# node.net
KiCad netlist of a schematic drawn in EAGLE
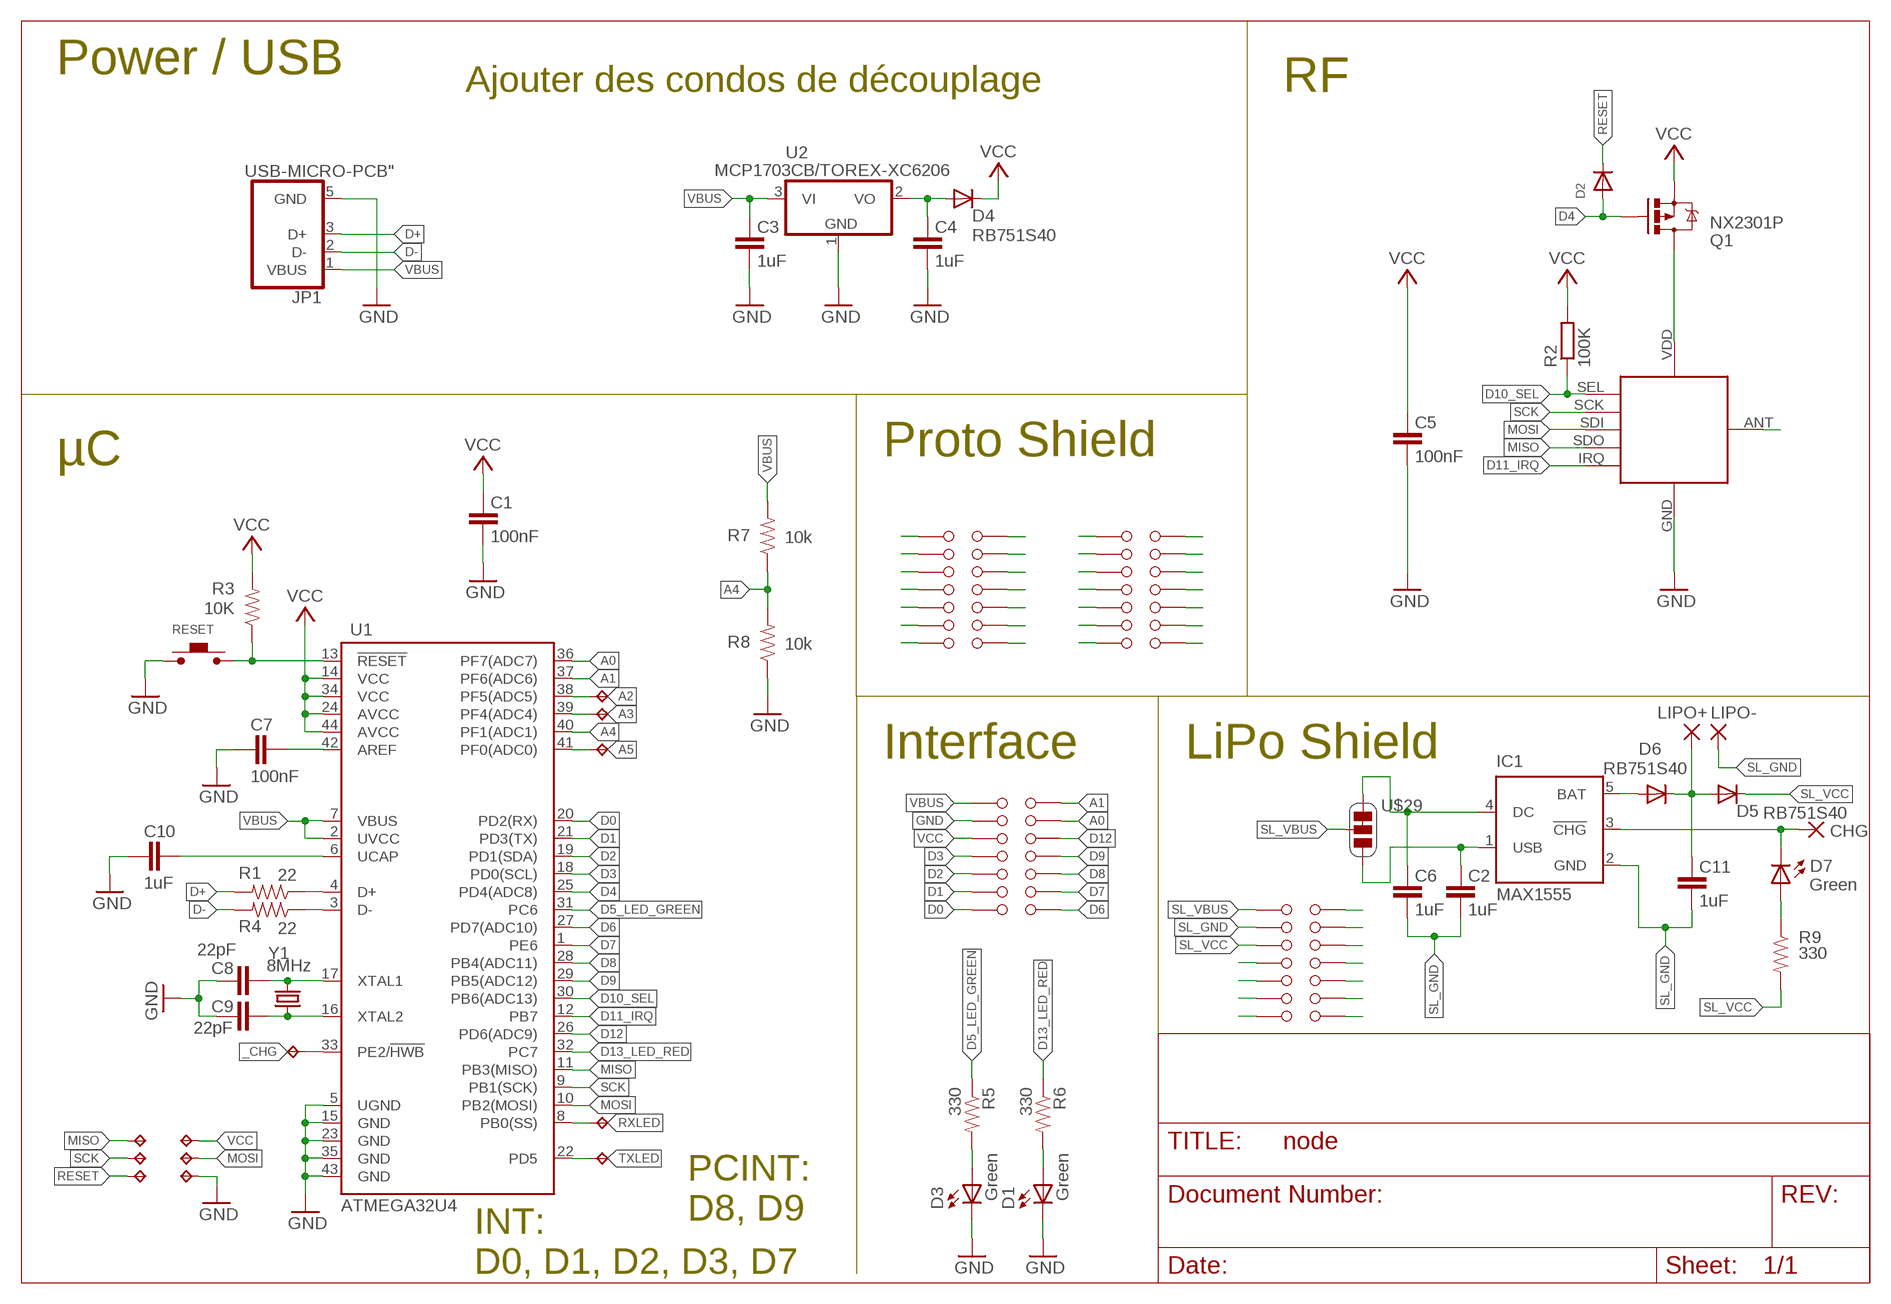
[diagram p0: schematic, sheet 1]

(export (version "E")
  (design (tool "Eeschema 10.0.6"))
  (components
    (comp (ref "C1")
      (value "100nF")
      (footprint "eagle-import:0402-CAP")
      (libsource (lib "eagle-import") (part "CAP0402-CAP"))
    )
    (comp (ref "C2")
      (value "1uF")
      (footprint "eagle-import:0402-CAP")
      (libsource (lib "eagle-import") (part "CAP0402-CAP"))
    )
    (comp (ref "C3")
      (value "1uF")
      (footprint "eagle-import:0402-CAP")
      (libsource (lib "eagle-import") (part "CAP0402-CAP"))
    )
    (comp (ref "C4")
      (value "1uF")
      (footprint "eagle-import:0402-CAP")
      (libsource (lib "eagle-import") (part "CAP0402-CAP"))
    )
    (comp (ref "C5")
      (value "100nF")
      (footprint "eagle-import:0402-CAP")
      (libsource (lib "eagle-import") (part "CAP0402-CAP"))
    )
    (comp (ref "C6")
      (value "1uF")
      (footprint "eagle-import:0402-CAP")
      (libsource (lib "eagle-import") (part "CAP0402-CAP"))
    )
    (comp (ref "C7")
      (value "100nF")
      (footprint "eagle-import:0402-CAP")
      (libsource (lib "eagle-import") (part "CAP0402-CAP"))
    )
    (comp (ref "C8")
      (value "22pF")
      (footprint "eagle-import:0402-CAP")
      (libsource (lib "eagle-import") (part "CAP0402-CAP"))
    )
    (comp (ref "C9")
      (value "22pF")
      (footprint "eagle-import:0402-CAP")
      (libsource (lib "eagle-import") (part "CAP0402-CAP"))
    )
    (comp (ref "C10")
      (value "1uF")
      (footprint "eagle-import:0402-CAP")
      (libsource (lib "eagle-import") (part "CAP0402-CAP"))
    )
    (comp (ref "C11")
      (value "1uF")
      (footprint "eagle-import:0402-CAP")
      (libsource (lib "eagle-import") (part "CAP0402-CAP"))
    )
    (comp (ref "CHG")
      (value "WIREPAD1,6/0,8")
      (footprint "eagle-import:1,6_0,8")
      (libsource (lib "eagle-import") (part "WIREPAD1,6/0,8"))
    )
    (comp (ref "D1")
      (value "Green")
      (footprint "eagle-import:LED-0603")
      (libsource (lib "eagle-import") (part "LED0603"))
    )
    (comp (ref "D2")
      (value "DIODESOD-323F")
      (footprint "eagle-import:SOD-323F")
      (libsource (lib "eagle-import") (part "DIODESOD-323F"))
    )
    (comp (ref "D3")
      (value "Green")
      (footprint "eagle-import:LED-0603")
      (libsource (lib "eagle-import") (part "LED0603"))
    )
    (comp (ref "D4")
      (value "RB751S40")
      (footprint "eagle-import:SOD523")
      (libsource (lib "eagle-import") (part "DIODE-SOD523"))
    )
    (comp (ref "D5")
      (value "RB751S40")
      (footprint "eagle-import:SOD523")
      (libsource (lib "eagle-import") (part "DIODE-SOD523"))
    )
    (comp (ref "D6")
      (value "RB751S40")
      (footprint "eagle-import:SOD523")
      (libsource (lib "eagle-import") (part "DIODE-SOD523"))
    )
    (comp (ref "D7")
      (value "Green")
      (footprint "eagle-import:LED-0603")
      (libsource (lib "eagle-import") (part "LED0603"))
    )
    (comp (ref "IC1")
      (value "MAX1555")
      (footprint "eagle-import:SOT23-5L")
      (fields (field (name "MF") "MAXIM") (field (name "MPN") "MAX1555EZK+T"))
      (libsource (lib "eagle-import") (part "MAX1555"))
    )
    (comp (ref "JP1")
      (value "USB-MICRO-PCB\"")
      (footprint "eagle-import:USB-MICRO-PCB")
      (libsource (lib "eagle-import") (part "USB-MICRO-PCB{dblquote}"))
    )
    (comp (ref "LIPO+")
      (value "WIREPAD1,6/0,8")
      (footprint "eagle-import:1,6_0,8")
      (libsource (lib "eagle-import") (part "WIREPAD1,6/0,8"))
    )
    (comp (ref "LIPO-")
      (value "WIREPAD1,6/0,8")
      (footprint "eagle-import:1,6_0,8")
      (libsource (lib "eagle-import") (part "WIREPAD1,6/0,8"))
    )
    (comp (ref "Q1")
      (value "NX2301P")
      (footprint "eagle-import:SOT23")
      (libsource (lib "eagle-import") (part "MOSFET-PCHANNEL"))
    )
    (comp (ref "R1")
      (value "22")
      (footprint "eagle-import:0402-RES")
      (libsource (lib "eagle-import") (part "RESISTOR0402-RES"))
    )
    (comp (ref "R2")
      (value "100K")
      (footprint "eagle-import:R0402")
      (libsource (lib "eagle-import") (part "R-EU_R0402"))
    )
    (comp (ref "R3")
      (value "10K")
      (footprint "eagle-import:0402-RES")
      (libsource (lib "eagle-import") (part "RESISTOR0402-RES"))
    )
    (comp (ref "R4")
      (value "22")
      (footprint "eagle-import:0402-RES")
      (libsource (lib "eagle-import") (part "RESISTOR0402-RES"))
    )
    (comp (ref "R5")
      (value "330")
      (footprint "eagle-import:0402-RES")
      (libsource (lib "eagle-import") (part "RESISTOR0402-RES"))
    )
    (comp (ref "R6")
      (value "330")
      (footprint "eagle-import:0402-RES")
      (libsource (lib "eagle-import") (part "RESISTOR0402-RES"))
    )
    (comp (ref "R7")
      (value "10k")
      (footprint "eagle-import:0402-RES")
      (libsource (lib "eagle-import") (part "RESISTOR0402-RES"))
    )
    (comp (ref "R8")
      (value "10k")
      (footprint "eagle-import:0402-RES")
      (libsource (lib "eagle-import") (part "RESISTOR0402-RES"))
    )
    (comp (ref "R9")
      (value "330")
      (footprint "eagle-import:0402-RES")
      (libsource (lib "eagle-import") (part "RESISTOR0402-RES"))
    )
    (comp (ref "RESET")
      (value "MICROSWITCH")
      (footprint "eagle-import:MICROSWITCH")
      (libsource (lib "eagle-import") (part "MICROSWITCH"))
    )
    (comp (ref "RFMXX")
      (value "RFM12B_MINPADS")
      (footprint "eagle-import:RFM12B-MINPADS")
      (libsource (lib "eagle-import") (part "RFM12B_MINPADS"))
    )
    (comp (ref "TP1")
      (value "TPTP13R")
      (footprint "eagle-import:TP13R")
      (libsource (lib "eagle-import") (part "TPTP13R"))
    )
    (comp (ref "TP2")
      (value "TPTP13R")
      (footprint "eagle-import:TP13R")
      (libsource (lib "eagle-import") (part "TPTP13R"))
    )
    (comp (ref "TP3")
      (value "TPTP13R")
      (footprint "eagle-import:TP13R")
      (libsource (lib "eagle-import") (part "TPTP13R"))
    )
    (comp (ref "TP4")
      (value "TPTP13R")
      (footprint "eagle-import:TP13R")
      (libsource (lib "eagle-import") (part "TPTP13R"))
    )
    (comp (ref "TP5")
      (value "TPTP13R")
      (footprint "eagle-import:TP13R")
      (libsource (lib "eagle-import") (part "TPTP13R"))
    )
    (comp (ref "TP7")
      (value "TPTP08R")
      (footprint "eagle-import:TP08R")
      (libsource (lib "eagle-import") (part "TPTP08R"))
    )
    (comp (ref "TP8")
      (value "TPTP08R")
      (footprint "eagle-import:TP08R")
      (libsource (lib "eagle-import") (part "TPTP08R"))
    )
    (comp (ref "TP9")
      (value "TPTP08R")
      (footprint "eagle-import:TP08R")
      (libsource (lib "eagle-import") (part "TPTP08R"))
    )
    (comp (ref "TP10")
      (value "TPTP08R")
      (footprint "eagle-import:TP08R")
      (libsource (lib "eagle-import") (part "TPTP08R"))
    )
    (comp (ref "TP11")
      (value "TPTP08R")
      (footprint "eagle-import:TP08R")
      (libsource (lib "eagle-import") (part "TPTP08R"))
    )
    (comp (ref "TP12")
      (value "TPTP08R")
      (footprint "eagle-import:TP08R")
      (libsource (lib "eagle-import") (part "TPTP08R"))
    )
    (comp (ref "TP14")
      (value "TPTP13R")
      (footprint "eagle-import:TP13R")
      (libsource (lib "eagle-import") (part "TPTP13R"))
    )
    (comp (ref "U$1")
      (value "IOPAD")
      (footprint "eagle-import:IOPAD")
      (libsource (lib "eagle-import") (part "IOPAD"))
    )
    (comp (ref "U$2")
      (value "IOPAD")
      (footprint "eagle-import:IOPAD")
      (libsource (lib "eagle-import") (part "IOPAD"))
    )
    (comp (ref "U$3")
      (value "IOPAD")
      (footprint "eagle-import:IOPAD")
      (libsource (lib "eagle-import") (part "IOPAD"))
    )
    (comp (ref "U$4")
      (value "IOPAD")
      (footprint "eagle-import:IOPAD")
      (libsource (lib "eagle-import") (part "IOPAD"))
    )
    (comp (ref "U$5")
      (value "IOPAD")
      (footprint "eagle-import:IOPAD")
      (libsource (lib "eagle-import") (part "IOPAD"))
    )
    (comp (ref "U$6")
      (value "IOPAD")
      (footprint "eagle-import:IOPAD")
      (libsource (lib "eagle-import") (part "IOPAD"))
    )
    (comp (ref "U$7")
      (value "IOPAD")
      (footprint "eagle-import:IOPAD")
      (libsource (lib "eagle-import") (part "IOPAD"))
    )
    (comp (ref "U$8")
      (value "IOPAD")
      (footprint "eagle-import:IOPAD")
      (libsource (lib "eagle-import") (part "IOPAD"))
    )
    (comp (ref "U$9")
      (value "IOPAD")
      (footprint "eagle-import:IOPAD")
      (libsource (lib "eagle-import") (part "IOPAD"))
    )
    (comp (ref "U$10")
      (value "IOPAD")
      (footprint "eagle-import:IOPAD")
      (libsource (lib "eagle-import") (part "IOPAD"))
    )
    (comp (ref "U$11")
      (value "IOPAD")
      (footprint "eagle-import:IOPAD")
      (libsource (lib "eagle-import") (part "IOPAD"))
    )
    (comp (ref "U$12")
      (value "IOPAD")
      (footprint "eagle-import:IOPAD")
      (libsource (lib "eagle-import") (part "IOPAD"))
    )
    (comp (ref "U$13")
      (value "IOPAD")
      (footprint "eagle-import:IOPAD")
      (libsource (lib "eagle-import") (part "IOPAD"))
    )
    (comp (ref "U$14")
      (value "IOPAD")
      (footprint "eagle-import:IOPAD")
      (libsource (lib "eagle-import") (part "IOPAD"))
    )
    (comp (ref "U$15")
      (value "IOPAD")
      (footprint "eagle-import:IOPAD")
      (libsource (lib "eagle-import") (part "IOPAD"))
    )
    (comp (ref "U$16")
      (value "IOPAD")
      (footprint "eagle-import:IOPAD")
      (libsource (lib "eagle-import") (part "IOPAD"))
    )
    (comp (ref "U$17")
      (value "IOPAD")
      (footprint "eagle-import:IOPAD")
      (libsource (lib "eagle-import") (part "IOPAD"))
    )
    (comp (ref "U$18")
      (value "IOPAD")
      (footprint "eagle-import:IOPAD")
      (libsource (lib "eagle-import") (part "IOPAD"))
    )
    (comp (ref "U$19")
      (value "IOPAD")
      (footprint "eagle-import:IOPAD")
      (libsource (lib "eagle-import") (part "IOPAD"))
    )
    (comp (ref "U$20")
      (value "IOPAD")
      (footprint "eagle-import:IOPAD")
      (libsource (lib "eagle-import") (part "IOPAD"))
    )
    (comp (ref "U$21")
      (value "IOPAD")
      (footprint "eagle-import:IOPAD")
      (libsource (lib "eagle-import") (part "IOPAD"))
    )
    (comp (ref "U$22")
      (value "IOPAD")
      (footprint "eagle-import:IOPAD")
      (libsource (lib "eagle-import") (part "IOPAD"))
    )
    (comp (ref "U$23")
      (value "IOPAD")
      (footprint "eagle-import:IOPAD")
      (libsource (lib "eagle-import") (part "IOPAD"))
    )
    (comp (ref "U$24")
      (value "IOPAD")
      (footprint "eagle-import:IOPAD")
      (libsource (lib "eagle-import") (part "IOPAD"))
    )
    (comp (ref "U$25")
      (value "IOPAD")
      (footprint "eagle-import:IOPAD")
      (libsource (lib "eagle-import") (part "IOPAD"))
    )
    (comp (ref "U$26")
      (value "IOPAD")
      (footprint "eagle-import:IOPAD")
      (libsource (lib "eagle-import") (part "IOPAD"))
    )
    (comp (ref "U$27")
      (value "IOPAD")
      (footprint "eagle-import:IOPAD")
      (libsource (lib "eagle-import") (part "IOPAD"))
    )
    (comp (ref "U$28")
      (value "IOPAD")
      (footprint "eagle-import:IOPAD")
      (libsource (lib "eagle-import") (part "IOPAD"))
    )
    (comp (ref "U$29")
      (value "UJUMPER-SHORT")
      (footprint "eagle-import:UJUMPER-SHORT")
      (libsource (lib "eagle-import") (part "UJUMPER-SHORT"))
    )
    (comp (ref "U$30")
      (value "IOPAD")
      (footprint "eagle-import:IOPAD")
      (libsource (lib "eagle-import") (part "IOPAD"))
    )
    (comp (ref "U$31")
      (value "IOPAD")
      (footprint "eagle-import:IOPAD")
      (libsource (lib "eagle-import") (part "IOPAD"))
    )
    (comp (ref "U$32")
      (value "IOPAD")
      (footprint "eagle-import:IOPAD")
      (libsource (lib "eagle-import") (part "IOPAD"))
    )
    (comp (ref "U$33")
      (value "IOPAD")
      (footprint "eagle-import:IOPAD")
      (libsource (lib "eagle-import") (part "IOPAD"))
    )
    (comp (ref "U$34")
      (value "IOPAD")
      (footprint "eagle-import:IOPAD")
      (libsource (lib "eagle-import") (part "IOPAD"))
    )
    (comp (ref "U$35")
      (value "IOPAD")
      (footprint "eagle-import:IOPAD")
      (libsource (lib "eagle-import") (part "IOPAD"))
    )
    (comp (ref "U$36")
      (value "IOPAD")
      (footprint "eagle-import:IOPAD")
      (libsource (lib "eagle-import") (part "IOPAD"))
    )
    (comp (ref "U$37")
      (value "IOPAD")
      (footprint "eagle-import:IOPAD")
      (libsource (lib "eagle-import") (part "IOPAD"))
    )
    (comp (ref "U$38")
      (value "IOPAD")
      (footprint "eagle-import:IOPAD")
      (libsource (lib "eagle-import") (part "IOPAD"))
    )
    (comp (ref "U$39")
      (value "IOPAD")
      (footprint "eagle-import:IOPAD")
      (libsource (lib "eagle-import") (part "IOPAD"))
    )
    (comp (ref "U$40")
      (value "IOPAD")
      (footprint "eagle-import:IOPAD")
      (libsource (lib "eagle-import") (part "IOPAD"))
    )
    (comp (ref "U$41")
      (value "IOPAD")
      (footprint "eagle-import:IOPAD")
      (libsource (lib "eagle-import") (part "IOPAD"))
    )
    (comp (ref "U$42")
      (value "IOPAD")
      (footprint "eagle-import:IOPAD")
      (libsource (lib "eagle-import") (part "IOPAD"))
    )
    (comp (ref "U$43")
      (value "IOPAD")
      (footprint "eagle-import:IOPAD")
      (libsource (lib "eagle-import") (part "IOPAD"))
    )
    (comp (ref "U$44")
      (value "IOPAD")
      (footprint "eagle-import:IOPAD")
      (libsource (lib "eagle-import") (part "IOPAD"))
    )
    (comp (ref "U$45")
      (value "IOPAD")
      (footprint "eagle-import:IOPAD")
      (libsource (lib "eagle-import") (part "IOPAD"))
    )
    (comp (ref "U$46")
      (value "IOPAD")
      (footprint "eagle-import:IOPAD")
      (libsource (lib "eagle-import") (part "IOPAD"))
    )
    (comp (ref "U$47")
      (value "IOPAD")
      (footprint "eagle-import:IOPAD")
      (libsource (lib "eagle-import") (part "IOPAD"))
    )
    (comp (ref "U$48")
      (value "IOPAD")
      (footprint "eagle-import:IOPAD")
      (libsource (lib "eagle-import") (part "IOPAD"))
    )
    (comp (ref "U$49")
      (value "IOPAD")
      (footprint "eagle-import:IOPAD")
      (libsource (lib "eagle-import") (part "IOPAD"))
    )
    (comp (ref "U$50")
      (value "IOPAD")
      (footprint "eagle-import:IOPAD")
      (libsource (lib "eagle-import") (part "IOPAD"))
    )
    (comp (ref "U$51")
      (value "IOPAD")
      (footprint "eagle-import:IOPAD")
      (libsource (lib "eagle-import") (part "IOPAD"))
    )
    (comp (ref "U$52")
      (value "IOPAD")
      (footprint "eagle-import:IOPAD")
      (libsource (lib "eagle-import") (part "IOPAD"))
    )
    (comp (ref "U$53")
      (value "IOPAD")
      (footprint "eagle-import:IOPAD")
      (libsource (lib "eagle-import") (part "IOPAD"))
    )
    (comp (ref "U$54")
      (value "IOPAD")
      (footprint "eagle-import:IOPAD")
      (libsource (lib "eagle-import") (part "IOPAD"))
    )
    (comp (ref "U$55")
      (value "IOPAD")
      (footprint "eagle-import:IOPAD")
      (libsource (lib "eagle-import") (part "IOPAD"))
    )
    (comp (ref "U$56")
      (value "IOPAD")
      (footprint "eagle-import:IOPAD")
      (libsource (lib "eagle-import") (part "IOPAD"))
    )
    (comp (ref "U$57")
      (value "IOPAD")
      (footprint "eagle-import:IOPAD")
      (libsource (lib "eagle-import") (part "IOPAD"))
    )
    (comp (ref "U1")
      (value "ATMEGA32U4")
      (footprint "eagle-import:QFN-44-NOPAD")
      (libsource (lib "eagle-import") (part "ATMEGA32U4QFN2"))
    )
    (comp (ref "U2")
      (value "MCP1703CB/TOREX-XC6206")
      (footprint "eagle-import:SOT23")
      (libsource (lib "eagle-import") (part "MCP1703CB"))
    )
    (comp (ref "Y1")
      (value "8MHz")
      (footprint "eagle-import:CRYSTAL-SMD-5X3")
      (libsource (lib "eagle-import") (part "CRYSTAL5X3"))
    )
  )
  (nets
    (net (code "1") (name "A0") (class "Default")
      (node (ref "U$9") (pin "P$1") (pinfunction "P$1_P$1") (pintype "bidirectional"))
      (node (ref "U1") (pin "36") (pinfunction "PF7(ADC7)_36") (pintype "bidirectional"))
    )
    (net (code "2") (name "A1") (class "Default")
      (node (ref "U$8") (pin "P$1") (pinfunction "P$1_P$1") (pintype "bidirectional"))
      (node (ref "U1") (pin "37") (pinfunction "PF6(ADC6)_37") (pintype "bidirectional"))
    )
    (net (code "3") (name "A2") (class "Default")
      (node (ref "TP7") (pin "TP") (pinfunction "TP_TP") (pintype "input"))
      (node (ref "U1") (pin "38") (pinfunction "PF5(ADC5)_38") (pintype "bidirectional"))
    )
    (net (code "4") (name "A3") (class "Default")
      (node (ref "TP8") (pin "TP") (pinfunction "TP_TP") (pintype "input"))
      (node (ref "U1") (pin "39") (pinfunction "PF4(ADC4)_39") (pintype "bidirectional"))
    )
    (net (code "5") (name "A4") (class "Default")
      (node (ref "R7") (pin "1") (pinfunction "1_1") (pintype "passive"))
      (node (ref "R8") (pin "2") (pinfunction "2_2") (pintype "passive"))
      (node (ref "U1") (pin "40") (pinfunction "PF1(ADC1)_40") (pintype "bidirectional"))
    )
    (net (code "6") (name "A5") (class "Default")
      (node (ref "TP10") (pin "TP") (pinfunction "TP_TP") (pintype "input"))
      (node (ref "U1") (pin "41") (pinfunction "PF0(ADC0)_41") (pintype "bidirectional"))
    )
    (net (code "7") (name "D+") (class "Default")
      (node (ref "JP1") (pin "3") (pinfunction "D+_3") (pintype "bidirectional"))
      (node (ref "R1") (pin "2") (pinfunction "2_2") (pintype "passive"))
    )
    (net (code "8") (name "D-") (class "Default")
      (node (ref "JP1") (pin "2") (pinfunction "D-_2") (pintype "bidirectional"))
      (node (ref "R4") (pin "2") (pinfunction "2_2") (pintype "passive"))
    )
    (net (code "9") (name "D0") (class "Default")
      (node (ref "U$2") (pin "P$1") (pinfunction "P$1_P$1") (pintype "bidirectional"))
      (node (ref "U1") (pin "20") (pinfunction "PD2(RX)_20") (pintype "bidirectional"))
    )
    (net (code "10") (name "D1") (class "Default")
      (node (ref "U$1") (pin "P$1") (pinfunction "P$1_P$1") (pintype "bidirectional"))
      (node (ref "U1") (pin "21") (pinfunction "PD3(TX)_21") (pintype "bidirectional"))
    )
    (net (code "11") (name "D2") (class "Default")
      (node (ref "U$3") (pin "P$1") (pinfunction "P$1_P$1") (pintype "bidirectional"))
      (node (ref "U1") (pin "19") (pinfunction "PD1(SDA)_19") (pintype "bidirectional"))
    )
    (net (code "12") (name "D3") (class "Default")
      (node (ref "U$4") (pin "P$1") (pinfunction "P$1_P$1") (pintype "bidirectional"))
      (node (ref "U1") (pin "18") (pinfunction "PD0(SCL)_18") (pintype "bidirectional"))
    )
    (net (code "13") (name "D4") (class "Default")
      (node (ref "D2") (pin "A") (pinfunction "A_A") (pintype "passive"))
      (node (ref "Q1") (pin "1") (pinfunction "G_1") (pintype "passive"))
      (node (ref "U1") (pin "25") (pinfunction "PD4(ADC8)_25") (pintype "bidirectional"))
    )
    (net (code "14") (name "D5_LED_GREEN") (class "Default")
      (node (ref "R5") (pin "1") (pinfunction "1_1") (pintype "passive"))
      (node (ref "U1") (pin "31") (pinfunction "PC6_31") (pintype "bidirectional"))
    )
    (net (code "15") (name "D6") (class "Default")
      (node (ref "U$14") (pin "P$1") (pinfunction "P$1_P$1") (pintype "bidirectional"))
      (node (ref "U1") (pin "27") (pinfunction "PD7(ADC10)_27") (pintype "bidirectional"))
    )
    (net (code "16") (name "D7") (class "Default")
      (node (ref "U$13") (pin "P$1") (pinfunction "P$1_P$1") (pintype "bidirectional"))
      (node (ref "U1") (pin "1") (pinfunction "PE6_1") (pintype "bidirectional"))
    )
    (net (code "17") (name "D8") (class "Default")
      (node (ref "U$12") (pin "P$1") (pinfunction "P$1_P$1") (pintype "bidirectional"))
      (node (ref "U1") (pin "28") (pinfunction "PB4(ADC11)_28") (pintype "bidirectional"))
    )
    (net (code "18") (name "D9") (class "Default")
      (node (ref "U$11") (pin "P$1") (pinfunction "P$1_P$1") (pintype "bidirectional"))
      (node (ref "U1") (pin "29") (pinfunction "PB5(ADC12)_29") (pintype "bidirectional"))
    )
    (net (code "19") (name "D10_SEL") (class "Default")
      (node (ref "R2") (pin "1") (pinfunction "1_1") (pintype "passive"))
      (node (ref "RFMXX") (pin "SEL") (pinfunction "SEL_SEL") (pintype "bidirectional"))
      (node (ref "U1") (pin "30") (pinfunction "PB6(ADC13)_30") (pintype "bidirectional"))
    )
    (net (code "20") (name "D11_IRQ") (class "Default")
      (node (ref "RFMXX") (pin "IRQ") (pinfunction "IRQ_IRQ") (pintype "bidirectional"))
      (node (ref "U1") (pin "12") (pinfunction "PB7_12") (pintype "bidirectional"))
    )
    (net (code "21") (name "D12") (class "Default")
      (node (ref "U$10") (pin "P$1") (pinfunction "P$1_P$1") (pintype "bidirectional"))
      (node (ref "U1") (pin "26") (pinfunction "PD6(ADC9)_26") (pintype "bidirectional"))
    )
    (net (code "22") (name "D13_LED_RED") (class "Default")
      (node (ref "R6") (pin "1") (pinfunction "1_1") (pintype "passive"))
      (node (ref "U1") (pin "32") (pinfunction "PC7_32") (pintype "bidirectional"))
    )
    (net (code "23") (name "GND") (class "Default")
      (node (ref "C1") (pin "1") (pinfunction "1_1") (pintype "passive"))
      (node (ref "C10") (pin "1") (pinfunction "1_1") (pintype "passive"))
      (node (ref "C3") (pin "1") (pinfunction "1_1") (pintype "passive"))
      (node (ref "C4") (pin "1") (pinfunction "1_1") (pintype "passive"))
      (node (ref "C5") (pin "1") (pinfunction "1_1") (pintype "passive"))
      (node (ref "C7") (pin "1") (pinfunction "1_1") (pintype "passive"))
      (node (ref "C8") (pin "2") (pinfunction "2_2") (pintype "passive"))
      (node (ref "C9") (pin "2") (pinfunction "2_2") (pintype "passive"))
      (node (ref "D1") (pin "C") (pinfunction "C_C") (pintype "passive"))
      (node (ref "D3") (pin "C") (pinfunction "C_C") (pintype "passive"))
      (node (ref "JP1") (pin "5") (pinfunction "GND_5") (pintype "bidirectional"))
      (node (ref "R8") (pin "1") (pinfunction "1_1") (pintype "passive"))
      (node (ref "RESET") (pin "P$1") (pinfunction "P$1_P$1") (pintype "bidirectional"))
      (node (ref "RFMXX") (pin "GND") (pinfunction "GND_GND") (pintype "bidirectional"))
      (node (ref "TP5") (pin "TP") (pinfunction "TP_TP") (pintype "input"))
      (node (ref "U$6") (pin "P$1") (pinfunction "P$1_P$1") (pintype "bidirectional"))
      (node (ref "U1") (pin "15") (pinfunction "GND_15") (pintype "bidirectional"))
      (node (ref "U1") (pin "23") (pinfunction "GND_23") (pintype "bidirectional"))
      (node (ref "U1") (pin "35") (pinfunction "GND_35") (pintype "bidirectional"))
      (node (ref "U1") (pin "43") (pinfunction "GND_43") (pintype "bidirectional"))
      (node (ref "U1") (pin "5") (pinfunction "UGND_5") (pintype "bidirectional"))
      (node (ref "U2") (pin "1") (pinfunction "GND_1") (pintype "passive"))
    )
    (net (code "24") (name "MISO") (class "Default")
      (node (ref "RFMXX") (pin "SDO") (pinfunction "SDO/MISO_SDO") (pintype "bidirectional"))
      (node (ref "TP14") (pin "TP") (pinfunction "TP_TP") (pintype "input"))
      (node (ref "U1") (pin "11") (pinfunction "PB3(MISO)_11") (pintype "bidirectional"))
    )
    (net (code "25") (name "MOSI") (class "Default")
      (node (ref "RFMXX") (pin "SDI") (pinfunction "SDI/MOSI_SDI") (pintype "bidirectional"))
      (node (ref "TP4") (pin "TP") (pinfunction "TP_TP") (pintype "input"))
      (node (ref "U1") (pin "10") (pinfunction "PB2(MOSI)_10") (pintype "bidirectional"))
    )
    (net (code "26") (name "Net-(CHG-P)") (class "Default")
      (node (ref "CHG") (pin "1") (pinfunction "P_1") (pintype "passive"))
      (node (ref "D7") (pin "C") (pinfunction "C_C") (pintype "passive"))
      (node (ref "IC1") (pin "3") (pinfunction "~{CHG}_3") (pintype "output"))
    )
    (net (code "27") (name "Net-(D1-PadA)") (class "Default")
      (node (ref "D1") (pin "A") (pinfunction "A_A") (pintype "passive"))
      (node (ref "R6") (pin "2") (pinfunction "2_2") (pintype "passive"))
    )
    (net (code "28") (name "Net-(D3-PadA)") (class "Default")
      (node (ref "D3") (pin "A") (pinfunction "A_A") (pintype "passive"))
      (node (ref "R5") (pin "2") (pinfunction "2_2") (pintype "passive"))
    )
    (net (code "29") (name "Net-(D7-PadA)") (class "Default")
      (node (ref "D7") (pin "A") (pinfunction "A_A") (pintype "passive"))
      (node (ref "R9") (pin "1") (pinfunction "1_1") (pintype "passive"))
    )
    (net (code "30") (name "Net-(IC1-BAT)") (class "Default")
      (node (ref "D6") (pin "A") (pinfunction "A_A") (pintype "passive"))
      (node (ref "IC1") (pin "5") (pinfunction "BAT_5") (pintype "passive"))
    )
    (net (code "31") (name "Net-(IC1-DC)") (class "Default")
      (node (ref "C6") (pin "2") (pinfunction "2_2") (pintype "passive"))
      (node (ref "IC1") (pin "4") (pinfunction "DC_4") (pintype "input"))
      (node (ref "U$29") (pin "C0") (pinfunction "C0_C0") (pintype "bidirectional"))
    )
    (net (code "32") (name "Net-(IC1-USB)") (class "Default")
      (node (ref "C2") (pin "2") (pinfunction "2_2") (pintype "passive"))
      (node (ref "IC1") (pin "1") (pinfunction "USB_1") (pintype "input"))
      (node (ref "U$29") (pin "C1") (pinfunction "C1_C1") (pintype "bidirectional"))
    )
    (net (code "33") (name "Net-(LIPO+-P)") (class "Default")
      (node (ref "C11") (pin "2") (pinfunction "2_2") (pintype "passive"))
      (node (ref "D5") (pin "A") (pinfunction "A_A") (pintype "passive"))
      (node (ref "D6") (pin "C") (pinfunction "C_C") (pintype "passive"))
      (node (ref "LIPO+") (pin "1") (pinfunction "P_1") (pintype "passive"))
    )
    (net (code "34") (name "Net-(Q1-D)") (class "Default")
      (node (ref "Q1") (pin "3") (pinfunction "D_3") (pintype "passive"))
      (node (ref "RFMXX") (pin "VDD") (pinfunction "VDD_VDD") (pintype "bidirectional"))
    )
    (net (code "35") (name "Net-(U1-AREF)") (class "Default")
      (node (ref "C7") (pin "2") (pinfunction "2_2") (pintype "passive"))
      (node (ref "U1") (pin "42") (pinfunction "AREF_42") (pintype "bidirectional"))
    )
    (net (code "36") (name "Net-(U1-D+)") (class "Default")
      (node (ref "R1") (pin "1") (pinfunction "1_1") (pintype "passive"))
      (node (ref "U1") (pin "4") (pinfunction "D+_4") (pintype "bidirectional"))
    )
    (net (code "37") (name "Net-(U1-D-)") (class "Default")
      (node (ref "R4") (pin "1") (pinfunction "1_1") (pintype "passive"))
      (node (ref "U1") (pin "3") (pinfunction "D-_3") (pintype "bidirectional"))
    )
    (net (code "38") (name "Net-(U1-UCAP)") (class "Default")
      (node (ref "C10") (pin "2") (pinfunction "2_2") (pintype "passive"))
      (node (ref "U1") (pin "6") (pinfunction "UCAP_6") (pintype "bidirectional"))
    )
    (net (code "39") (name "Net-(U1-XTAL1)") (class "Default")
      (node (ref "C8") (pin "1") (pinfunction "1_1") (pintype "passive"))
      (node (ref "U1") (pin "17") (pinfunction "XTAL1_17") (pintype "bidirectional"))
      (node (ref "Y1") (pin "3") (pinfunction "2_3") (pintype "passive"))
    )
    (net (code "40") (name "Net-(U1-XTAL2)") (class "Default")
      (node (ref "C9") (pin "1") (pinfunction "1_1") (pintype "passive"))
      (node (ref "U1") (pin "16") (pinfunction "XTAL2_16") (pintype "bidirectional"))
      (node (ref "Y1") (pin "1") (pinfunction "1_1") (pintype "passive"))
    )
    (net (code "41") (name "Net-(U2-VO)") (class "Default")
      (node (ref "C4") (pin "2") (pinfunction "2_2") (pintype "passive"))
      (node (ref "D4") (pin "A") (pinfunction "A_A") (pintype "passive"))
      (node (ref "U2") (pin "2") (pinfunction "VO_2") (pintype "passive"))
    )
    (net (code "42") (name "RESET") (class "Default")
      (node (ref "D2") (pin "C") (pinfunction "C_C") (pintype "passive"))
      (node (ref "R3") (pin "1") (pinfunction "1_1") (pintype "passive"))
      (node (ref "RESET") (pin "P$2") (pinfunction "P$2_P$2") (pintype "bidirectional"))
      (node (ref "TP3") (pin "TP") (pinfunction "TP_TP") (pintype "input"))
      (node (ref "U1") (pin "13") (pinfunction "~{RESET}_13") (pintype "bidirectional"))
    )
    (net (code "43") (name "RXLED") (class "Default")
      (node (ref "TP11") (pin "TP") (pinfunction "TP_TP") (pintype "input"))
      (node (ref "U1") (pin "8") (pinfunction "PB0(SS)_8") (pintype "bidirectional"))
    )
    (net (code "44") (name "SCK") (class "Default")
      (node (ref "RFMXX") (pin "SCK") (pinfunction "SCK_SCK") (pintype "bidirectional"))
      (node (ref "TP2") (pin "TP") (pinfunction "TP_TP") (pintype "input"))
      (node (ref "U1") (pin "9") (pinfunction "PB1(SCK)_9") (pintype "bidirectional"))
    )
    (net (code "45") (name "SL_GND") (class "Default")
      (node (ref "C11") (pin "1") (pinfunction "1_1") (pintype "passive"))
      (node (ref "C2") (pin "1") (pinfunction "1_1") (pintype "passive"))
      (node (ref "C6") (pin "1") (pinfunction "1_1") (pintype "passive"))
      (node (ref "IC1") (pin "2") (pinfunction "GND_2") (pintype "power_in"))
      (node (ref "LIPO-") (pin "1") (pinfunction "P_1") (pintype "passive"))
      (node (ref "U$31") (pin "P$1") (pinfunction "P$1_P$1") (pintype "bidirectional"))
    )
    (net (code "46") (name "SL_VBUS") (class "Default")
      (node (ref "U$29") (pin "COM") (pinfunction "COM_COM") (pintype "bidirectional"))
      (node (ref "U$30") (pin "P$1") (pinfunction "P$1_P$1") (pintype "bidirectional"))
    )
    (net (code "47") (name "SL_VCC") (class "Default")
      (node (ref "D5") (pin "C") (pinfunction "C_C") (pintype "passive"))
      (node (ref "R9") (pin "2") (pinfunction "2_2") (pintype "passive"))
      (node (ref "U$32") (pin "P$1") (pinfunction "P$1_P$1") (pintype "bidirectional"))
    )
    (net (code "48") (name "TXLED") (class "Default")
      (node (ref "TP9") (pin "TP") (pinfunction "TP_TP") (pintype "input"))
      (node (ref "U1") (pin "22") (pinfunction "PD5_22") (pintype "bidirectional"))
    )
    (net (code "49") (name "VBUS") (class "Default")
      (node (ref "C3") (pin "2") (pinfunction "2_2") (pintype "passive"))
      (node (ref "JP1") (pin "1") (pinfunction "VBUS_1") (pintype "bidirectional"))
      (node (ref "R7") (pin "2") (pinfunction "2_2") (pintype "passive"))
      (node (ref "U$7") (pin "P$1") (pinfunction "P$1_P$1") (pintype "bidirectional"))
      (node (ref "U1") (pin "2") (pinfunction "UVCC_2") (pintype "bidirectional"))
      (node (ref "U1") (pin "7") (pinfunction "VBUS_7") (pintype "bidirectional"))
      (node (ref "U2") (pin "3") (pinfunction "VI_3") (pintype "input"))
    )
    (net (code "50") (name "VCC") (class "Default")
      (node (ref "C1") (pin "2") (pinfunction "2_2") (pintype "passive"))
      (node (ref "C5") (pin "2") (pinfunction "2_2") (pintype "passive"))
      (node (ref "D4") (pin "C") (pinfunction "C_C") (pintype "passive"))
      (node (ref "Q1") (pin "2") (pinfunction "S_2") (pintype "passive"))
      (node (ref "R2") (pin "2") (pinfunction "2_2") (pintype "passive"))
      (node (ref "R3") (pin "2") (pinfunction "2_2") (pintype "passive"))
      (node (ref "TP1") (pin "TP") (pinfunction "TP_TP") (pintype "input"))
      (node (ref "U$5") (pin "P$1") (pinfunction "P$1_P$1") (pintype "bidirectional"))
      (node (ref "U1") (pin "14") (pinfunction "VCC_14") (pintype "bidirectional"))
      (node (ref "U1") (pin "24") (pinfunction "AVCC_24") (pintype "bidirectional"))
      (node (ref "U1") (pin "34") (pinfunction "VCC_34") (pintype "bidirectional"))
      (node (ref "U1") (pin "44") (pinfunction "AVCC_44") (pintype "bidirectional"))
    )
    (net (code "51") (name "_CHG") (class "Default")
      (node (ref "TP12") (pin "TP") (pinfunction "TP_TP") (pintype "input"))
      (node (ref "U1") (pin "33") (pinfunction "PE2/~{HWB}_33") (pintype "bidirectional"))
    )
    (net (code "52") (name "unconnected-(RFMXX-PadANT)") (class "Default")
      (node (ref "RFMXX") (pin "ANT") (pinfunction "ANT_ANT") (pintype "bidirectional"))
    )
    (net (code "53") (name "unconnected-(U$15-PadP$1)") (class "Default")
      (node (ref "U$15") (pin "P$1") (pinfunction "P$1_P$1") (pintype "bidirectional"))
    )
    (net (code "54") (name "unconnected-(U$16-PadP$1)") (class "Default")
      (node (ref "U$16") (pin "P$1") (pinfunction "P$1_P$1") (pintype "bidirectional"))
    )
    (net (code "55") (name "unconnected-(U$17-PadP$1)") (class "Default")
      (node (ref "U$17") (pin "P$1") (pinfunction "P$1_P$1") (pintype "bidirectional"))
    )
    (net (code "56") (name "unconnected-(U$18-PadP$1)") (class "Default")
      (node (ref "U$18") (pin "P$1") (pinfunction "P$1_P$1") (pintype "bidirectional"))
    )
    (net (code "57") (name "unconnected-(U$19-PadP$1)") (class "Default")
      (node (ref "U$19") (pin "P$1") (pinfunction "P$1_P$1") (pintype "bidirectional"))
    )
    (net (code "58") (name "unconnected-(U$20-PadP$1)") (class "Default")
      (node (ref "U$20") (pin "P$1") (pinfunction "P$1_P$1") (pintype "bidirectional"))
    )
    (net (code "59") (name "unconnected-(U$21-PadP$1)") (class "Default")
      (node (ref "U$21") (pin "P$1") (pinfunction "P$1_P$1") (pintype "bidirectional"))
    )
    (net (code "60") (name "unconnected-(U$22-PadP$1)") (class "Default")
      (node (ref "U$22") (pin "P$1") (pinfunction "P$1_P$1") (pintype "bidirectional"))
    )
    (net (code "61") (name "unconnected-(U$23-PadP$1)") (class "Default")
      (node (ref "U$23") (pin "P$1") (pinfunction "P$1_P$1") (pintype "bidirectional"))
    )
    (net (code "62") (name "unconnected-(U$24-PadP$1)") (class "Default")
      (node (ref "U$24") (pin "P$1") (pinfunction "P$1_P$1") (pintype "bidirectional"))
    )
    (net (code "63") (name "unconnected-(U$25-PadP$1)") (class "Default")
      (node (ref "U$25") (pin "P$1") (pinfunction "P$1_P$1") (pintype "bidirectional"))
    )
    (net (code "64") (name "unconnected-(U$26-PadP$1)") (class "Default")
      (node (ref "U$26") (pin "P$1") (pinfunction "P$1_P$1") (pintype "bidirectional"))
    )
    (net (code "65") (name "unconnected-(U$27-PadP$1)") (class "Default")
      (node (ref "U$27") (pin "P$1") (pinfunction "P$1_P$1") (pintype "bidirectional"))
    )
    (net (code "66") (name "unconnected-(U$28-PadP$1)") (class "Default")
      (node (ref "U$28") (pin "P$1") (pinfunction "P$1_P$1") (pintype "bidirectional"))
    )
    (net (code "67") (name "unconnected-(U$33-PadP$1)") (class "Default")
      (node (ref "U$33") (pin "P$1") (pinfunction "P$1_P$1") (pintype "bidirectional"))
    )
    (net (code "68") (name "unconnected-(U$34-PadP$1)") (class "Default")
      (node (ref "U$34") (pin "P$1") (pinfunction "P$1_P$1") (pintype "bidirectional"))
    )
    (net (code "69") (name "unconnected-(U$35-PadP$1)") (class "Default")
      (node (ref "U$35") (pin "P$1") (pinfunction "P$1_P$1") (pintype "bidirectional"))
    )
    (net (code "70") (name "unconnected-(U$36-PadP$1)") (class "Default")
      (node (ref "U$36") (pin "P$1") (pinfunction "P$1_P$1") (pintype "bidirectional"))
    )
    (net (code "71") (name "unconnected-(U$37-PadP$1)") (class "Default")
      (node (ref "U$37") (pin "P$1") (pinfunction "P$1_P$1") (pintype "bidirectional"))
    )
    (net (code "72") (name "unconnected-(U$38-PadP$1)") (class "Default")
      (node (ref "U$38") (pin "P$1") (pinfunction "P$1_P$1") (pintype "bidirectional"))
    )
    (net (code "73") (name "unconnected-(U$39-PadP$1)") (class "Default")
      (node (ref "U$39") (pin "P$1") (pinfunction "P$1_P$1") (pintype "bidirectional"))
    )
    (net (code "74") (name "unconnected-(U$40-PadP$1)") (class "Default")
      (node (ref "U$40") (pin "P$1") (pinfunction "P$1_P$1") (pintype "bidirectional"))
    )
    (net (code "75") (name "unconnected-(U$41-PadP$1)") (class "Default")
      (node (ref "U$41") (pin "P$1") (pinfunction "P$1_P$1") (pintype "bidirectional"))
    )
    (net (code "76") (name "unconnected-(U$42-PadP$1)") (class "Default")
      (node (ref "U$42") (pin "P$1") (pinfunction "P$1_P$1") (pintype "bidirectional"))
    )
    (net (code "77") (name "unconnected-(U$43-PadP$1)") (class "Default")
      (node (ref "U$43") (pin "P$1") (pinfunction "P$1_P$1") (pintype "bidirectional"))
    )
    (net (code "78") (name "unconnected-(U$44-PadP$1)") (class "Default")
      (node (ref "U$44") (pin "P$1") (pinfunction "P$1_P$1") (pintype "bidirectional"))
    )
    (net (code "79") (name "unconnected-(U$45-PadP$1)") (class "Default")
      (node (ref "U$45") (pin "P$1") (pinfunction "P$1_P$1") (pintype "bidirectional"))
    )
    (net (code "80") (name "unconnected-(U$46-PadP$1)") (class "Default")
      (node (ref "U$46") (pin "P$1") (pinfunction "P$1_P$1") (pintype "bidirectional"))
    )
    (net (code "81") (name "unconnected-(U$47-PadP$1)") (class "Default")
      (node (ref "U$47") (pin "P$1") (pinfunction "P$1_P$1") (pintype "bidirectional"))
    )
    (net (code "82") (name "unconnected-(U$48-PadP$1)") (class "Default")
      (node (ref "U$48") (pin "P$1") (pinfunction "P$1_P$1") (pintype "bidirectional"))
    )
    (net (code "83") (name "unconnected-(U$49-PadP$1)") (class "Default")
      (node (ref "U$49") (pin "P$1") (pinfunction "P$1_P$1") (pintype "bidirectional"))
    )
    (net (code "84") (name "unconnected-(U$50-PadP$1)") (class "Default")
      (node (ref "U$50") (pin "P$1") (pinfunction "P$1_P$1") (pintype "bidirectional"))
    )
    (net (code "85") (name "unconnected-(U$51-PadP$1)") (class "Default")
      (node (ref "U$51") (pin "P$1") (pinfunction "P$1_P$1") (pintype "bidirectional"))
    )
    (net (code "86") (name "unconnected-(U$52-PadP$1)") (class "Default")
      (node (ref "U$52") (pin "P$1") (pinfunction "P$1_P$1") (pintype "bidirectional"))
    )
    (net (code "87") (name "unconnected-(U$53-PadP$1)") (class "Default")
      (node (ref "U$53") (pin "P$1") (pinfunction "P$1_P$1") (pintype "bidirectional"))
    )
    (net (code "88") (name "unconnected-(U$54-PadP$1)") (class "Default")
      (node (ref "U$54") (pin "P$1") (pinfunction "P$1_P$1") (pintype "bidirectional"))
    )
    (net (code "89") (name "unconnected-(U$55-PadP$1)") (class "Default")
      (node (ref "U$55") (pin "P$1") (pinfunction "P$1_P$1") (pintype "bidirectional"))
    )
    (net (code "90") (name "unconnected-(U$56-PadP$1)") (class "Default")
      (node (ref "U$56") (pin "P$1") (pinfunction "P$1_P$1") (pintype "bidirectional"))
    )
    (net (code "91") (name "unconnected-(U$57-PadP$1)") (class "Default")
      (node (ref "U$57") (pin "P$1") (pinfunction "P$1_P$1") (pintype "bidirectional"))
    )
  )
)
